# Robert_Sullivan_Lamp.net
KiCad netlist of a schematic drawn in EAGLE
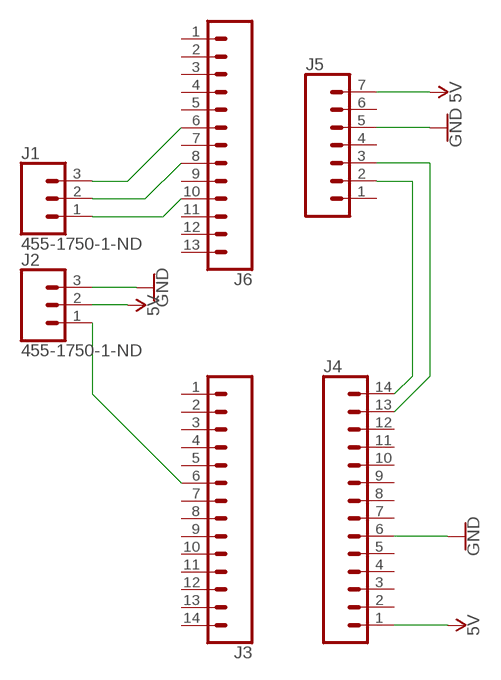
[diagram p0: schematic, sheet 1]

(export (version "E")
  (design (tool "Eeschema 10.0.6"))
  (components
    (comp (ref "J1")
      (value "455-1750-1-ND")
      (footprint "eagle-import:1X03")
      (libsource (lib "eagle-import") (part "CONN_03"))
    )
    (comp (ref "J2")
      (value "455-1750-1-ND")
      (footprint "eagle-import:1X03")
      (libsource (lib "eagle-import") (part "CONN_03"))
    )
    (comp (ref "J3")
      (value "CONN_14")
      (footprint "eagle-import:1X14")
      (libsource (lib "eagle-import") (part "CONN_14"))
    )
    (comp (ref "J4")
      (value "CONN_14")
      (footprint "eagle-import:1X14")
      (libsource (lib "eagle-import") (part "CONN_14"))
    )
    (comp (ref "J5")
      (value "CONN_07LOCK_LONGPADS")
      (footprint "eagle-import:1X07_LOCK_LONGPADS")
      (libsource (lib "eagle-import") (part "CONN_07LOCK_LONGPADS"))
    )
    (comp (ref "J6")
      (value "CONN_13")
      (footprint "eagle-import:1X13")
      (libsource (lib "eagle-import") (part "CONN_13"))
    )
  )
  (nets
    (net (code "1") (name "5V") (class "Default")
      (node (ref "J2") (pin "2") (pinfunction "2_2") (pintype "passive"))
      (node (ref "J4") (pin "1") (pinfunction "1_1") (pintype "passive"))
      (node (ref "J5") (pin "7") (pinfunction "7_7") (pintype "passive"))
    )
    (net (code "2") (name "GND") (class "Default")
      (node (ref "J2") (pin "3") (pinfunction "3_3") (pintype "passive"))
      (node (ref "J4") (pin "6") (pinfunction "6_6") (pintype "passive"))
      (node (ref "J5") (pin "5") (pinfunction "5_5") (pintype "passive"))
    )
    (net (code "3") (name "Net-(J1-Pad1)") (class "Default")
      (node (ref "J1") (pin "1") (pinfunction "1_1") (pintype "passive"))
      (node (ref "J6") (pin "10") (pinfunction "10_10") (pintype "passive"))
    )
    (net (code "4") (name "Net-(J1-Pad2)") (class "Default")
      (node (ref "J1") (pin "2") (pinfunction "2_2") (pintype "passive"))
      (node (ref "J6") (pin "8") (pinfunction "8_8") (pintype "passive"))
    )
    (net (code "5") (name "Net-(J1-Pad3)") (class "Default")
      (node (ref "J1") (pin "3") (pinfunction "3_3") (pintype "passive"))
      (node (ref "J6") (pin "6") (pinfunction "6_6") (pintype "passive"))
    )
    (net (code "6") (name "Net-(J2-Pad1)") (class "Default")
      (node (ref "J2") (pin "1") (pinfunction "1_1") (pintype "passive"))
      (node (ref "J3") (pin "6") (pinfunction "6_6") (pintype "passive"))
    )
    (net (code "7") (name "Net-(J4-Pad13)") (class "Default")
      (node (ref "J4") (pin "13") (pinfunction "13_13") (pintype "passive"))
      (node (ref "J5") (pin "3") (pinfunction "3_3") (pintype "passive"))
    )
    (net (code "8") (name "Net-(J4-Pad14)") (class "Default")
      (node (ref "J4") (pin "14") (pinfunction "14_14") (pintype "passive"))
      (node (ref "J5") (pin "2") (pinfunction "2_2") (pintype "passive"))
    )
    (net (code "9") (name "unconnected-(J3-Pad1)") (class "Default")
      (node (ref "J3") (pin "1") (pinfunction "1_1") (pintype "passive"))
    )
    (net (code "10") (name "unconnected-(J3-Pad2)") (class "Default")
      (node (ref "J3") (pin "2") (pinfunction "2_2") (pintype "passive"))
    )
    (net (code "11") (name "unconnected-(J3-Pad3)") (class "Default")
      (node (ref "J3") (pin "3") (pinfunction "3_3") (pintype "passive"))
    )
    (net (code "12") (name "unconnected-(J3-Pad4)") (class "Default")
      (node (ref "J3") (pin "4") (pinfunction "4_4") (pintype "passive"))
    )
    (net (code "13") (name "unconnected-(J3-Pad5)") (class "Default")
      (node (ref "J3") (pin "5") (pinfunction "5_5") (pintype "passive"))
    )
    (net (code "14") (name "unconnected-(J3-Pad7)") (class "Default")
      (node (ref "J3") (pin "7") (pinfunction "7_7") (pintype "passive"))
    )
    (net (code "15") (name "unconnected-(J3-Pad8)") (class "Default")
      (node (ref "J3") (pin "8") (pinfunction "8_8") (pintype "passive"))
    )
    (net (code "16") (name "unconnected-(J3-Pad9)") (class "Default")
      (node (ref "J3") (pin "9") (pinfunction "9_9") (pintype "passive"))
    )
    (net (code "17") (name "unconnected-(J3-Pad10)") (class "Default")
      (node (ref "J3") (pin "10") (pinfunction "10_10") (pintype "passive"))
    )
    (net (code "18") (name "unconnected-(J3-Pad11)") (class "Default")
      (node (ref "J3") (pin "11") (pinfunction "11_11") (pintype "passive"))
    )
    (net (code "19") (name "unconnected-(J3-Pad12)") (class "Default")
      (node (ref "J3") (pin "12") (pinfunction "12_12") (pintype "passive"))
    )
    (net (code "20") (name "unconnected-(J3-Pad13)") (class "Default")
      (node (ref "J3") (pin "13") (pinfunction "13_13") (pintype "passive"))
    )
    (net (code "21") (name "unconnected-(J3-Pad14)") (class "Default")
      (node (ref "J3") (pin "14") (pinfunction "14_14") (pintype "passive"))
    )
    (net (code "22") (name "unconnected-(J4-Pad2)") (class "Default")
      (node (ref "J4") (pin "2") (pinfunction "2_2") (pintype "passive"))
    )
    (net (code "23") (name "unconnected-(J4-Pad3)") (class "Default")
      (node (ref "J4") (pin "3") (pinfunction "3_3") (pintype "passive"))
    )
    (net (code "24") (name "unconnected-(J4-Pad4)") (class "Default")
      (node (ref "J4") (pin "4") (pinfunction "4_4") (pintype "passive"))
    )
    (net (code "25") (name "unconnected-(J4-Pad5)") (class "Default")
      (node (ref "J4") (pin "5") (pinfunction "5_5") (pintype "passive"))
    )
    (net (code "26") (name "unconnected-(J4-Pad7)") (class "Default")
      (node (ref "J4") (pin "7") (pinfunction "7_7") (pintype "passive"))
    )
    (net (code "27") (name "unconnected-(J4-Pad8)") (class "Default")
      (node (ref "J4") (pin "8") (pinfunction "8_8") (pintype "passive"))
    )
    (net (code "28") (name "unconnected-(J4-Pad9)") (class "Default")
      (node (ref "J4") (pin "9") (pinfunction "9_9") (pintype "passive"))
    )
    (net (code "29") (name "unconnected-(J4-Pad10)") (class "Default")
      (node (ref "J4") (pin "10") (pinfunction "10_10") (pintype "passive"))
    )
    (net (code "30") (name "unconnected-(J4-Pad11)") (class "Default")
      (node (ref "J4") (pin "11") (pinfunction "11_11") (pintype "passive"))
    )
    (net (code "31") (name "unconnected-(J4-Pad12)") (class "Default")
      (node (ref "J4") (pin "12") (pinfunction "12_12") (pintype "passive"))
    )
    (net (code "32") (name "unconnected-(J5-Pad1)") (class "Default")
      (node (ref "J5") (pin "1") (pinfunction "1_1") (pintype "passive"))
    )
    (net (code "33") (name "unconnected-(J5-Pad4)") (class "Default")
      (node (ref "J5") (pin "4") (pinfunction "4_4") (pintype "passive"))
    )
    (net (code "34") (name "unconnected-(J5-Pad6)") (class "Default")
      (node (ref "J5") (pin "6") (pinfunction "6_6") (pintype "passive"))
    )
    (net (code "35") (name "unconnected-(J6-Pad1)") (class "Default")
      (node (ref "J6") (pin "1") (pinfunction "1_1") (pintype "passive"))
    )
    (net (code "36") (name "unconnected-(J6-Pad2)") (class "Default")
      (node (ref "J6") (pin "2") (pinfunction "2_2") (pintype "passive"))
    )
    (net (code "37") (name "unconnected-(J6-Pad3)") (class "Default")
      (node (ref "J6") (pin "3") (pinfunction "3_3") (pintype "passive"))
    )
    (net (code "38") (name "unconnected-(J6-Pad4)") (class "Default")
      (node (ref "J6") (pin "4") (pinfunction "4_4") (pintype "passive"))
    )
    (net (code "39") (name "unconnected-(J6-Pad5)") (class "Default")
      (node (ref "J6") (pin "5") (pinfunction "5_5") (pintype "passive"))
    )
    (net (code "40") (name "unconnected-(J6-Pad7)") (class "Default")
      (node (ref "J6") (pin "7") (pinfunction "7_7") (pintype "passive"))
    )
    (net (code "41") (name "unconnected-(J6-Pad9)") (class "Default")
      (node (ref "J6") (pin "9") (pinfunction "9_9") (pintype "passive"))
    )
    (net (code "42") (name "unconnected-(J6-Pad11)") (class "Default")
      (node (ref "J6") (pin "11") (pinfunction "11_11") (pintype "passive"))
    )
    (net (code "43") (name "unconnected-(J6-Pad12)") (class "Default")
      (node (ref "J6") (pin "12") (pinfunction "12_12") (pintype "passive"))
    )
    (net (code "44") (name "unconnected-(J6-Pad13)") (class "Default")
      (node (ref "J6") (pin "13") (pinfunction "13_13") (pintype "passive"))
    )
  )
)
